# Grove_-_Directional_Light_Sensor_v1_0.net
KiCad netlist of a schematic drawn in EAGLE
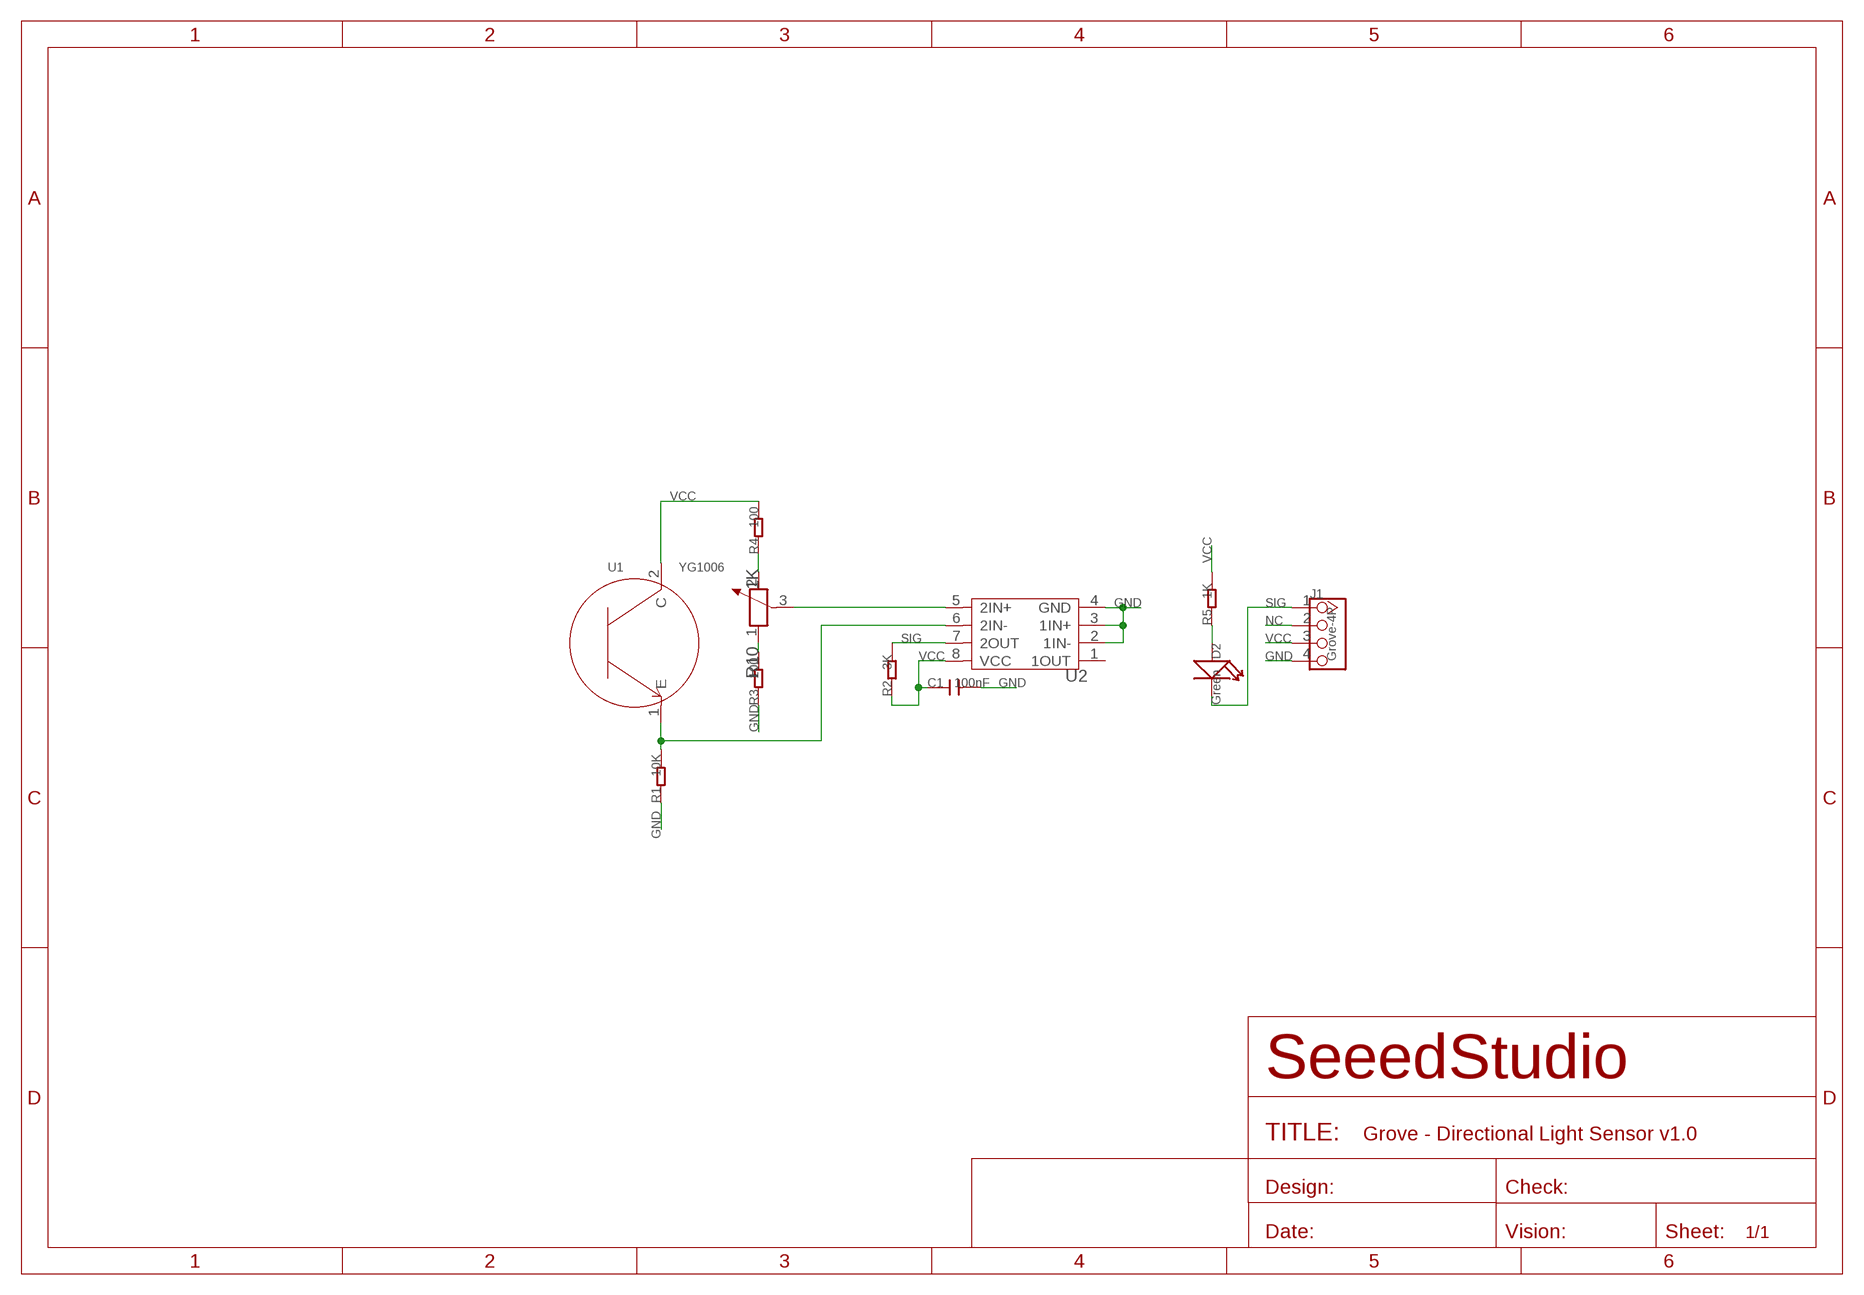
[diagram p0: schematic, sheet 1]

(export (version "E")
  (design (tool "Eeschema 10.0.6"))
  (components
    (comp (ref "C1")
      (value "100nF")
      (footprint "eagle-import:C0603")
      (libsource (lib "eagle-import") (part "C-0603"))
    )
    (comp (ref "D2")
      (value "Green")
      (footprint "eagle-import:LED-0603")
      (libsource (lib "eagle-import") (part "LED'0603'"))
    )
    (comp (ref "J1")
      (value "Grove-4P")
      (footprint "eagle-import:4P-2.0")
      (libsource (lib "eagle-import") (part "TWIG-4P-2.0-2.0"))
    )
    (comp (ref "R1")
      (value "10K")
      (footprint "eagle-import:R0603")
      (libsource (lib "eagle-import") (part "R-0603"))
    )
    (comp (ref "R2")
      (value "3K")
      (footprint "eagle-import:R0603")
      (libsource (lib "eagle-import") (part "R-0603"))
    )
    (comp (ref "R3")
      (value "100")
      (footprint "eagle-import:R0603")
      (libsource (lib "eagle-import") (part "R-0603"))
    )
    (comp (ref "R4")
      (value "100")
      (footprint "eagle-import:R0603")
      (libsource (lib "eagle-import") (part "R-0603"))
    )
    (comp (ref "R5")
      (value "1K")
      (footprint "eagle-import:R0603")
      (libsource (lib "eagle-import") (part "R-0603"))
    )
    (comp (ref "R10")
      (value "1K")
      (footprint "eagle-import:3P-SQUA-7X6.8")
      (libsource (lib "eagle-import") (part "R-POTENTIOMETER'3362'"))
    )
    (comp (ref "U1")
      (value "YG1006")
      (footprint "eagle-import:2P-2.54-5MM")
      (libsource (lib "eagle-import") (part "YG1006'YG1006'"))
    )
    (comp (ref "U2")
      (value "LM293D")
      (footprint "eagle-import:SOIC8-6.0")
      (libsource (lib "eagle-import") (part "LM293D"))
    )
  )
  (nets
    (net (code "1") (name "/GND") (class "Default")
      (node (ref "C1") (pin "2") (pinfunction "2_2") (pintype "passive"))
      (node (ref "J1") (pin "4") (pinfunction "4_4") (pintype "bidirectional"))
      (node (ref "R1") (pin "1") (pinfunction "1_1") (pintype "passive"))
      (node (ref "R3") (pin "1") (pinfunction "1_1") (pintype "passive"))
      (node (ref "U2") (pin "2") (pinfunction "1IN-_2") (pintype "input"))
      (node (ref "U2") (pin "3") (pinfunction "1IN+_3") (pintype "input"))
      (node (ref "U2") (pin "4") (pinfunction "GND_4") (pintype "power_in"))
    )
    (net (code "2") (name "/NC") (class "Default")
      (node (ref "J1") (pin "2") (pinfunction "2_2") (pintype "bidirectional"))
    )
    (net (code "3") (name "/SIG") (class "Default")
      (node (ref "D2") (pin "-") (pinfunction "-_-") (pintype "passive"))
      (node (ref "J1") (pin "1") (pinfunction "1_1") (pintype "bidirectional"))
      (node (ref "R2") (pin "2") (pinfunction "2_2") (pintype "passive"))
      (node (ref "U2") (pin "7") (pinfunction "2OUT_7") (pintype "output"))
    )
    (net (code "4") (name "/VCC") (class "Default")
      (node (ref "C1") (pin "1") (pinfunction "1_1") (pintype "passive"))
      (node (ref "J1") (pin "3") (pinfunction "3_3") (pintype "bidirectional"))
      (node (ref "R2") (pin "1") (pinfunction "1_1") (pintype "passive"))
      (node (ref "R4") (pin "2") (pinfunction "2_2") (pintype "passive"))
      (node (ref "R5") (pin "2") (pinfunction "2_2") (pintype "passive"))
      (node (ref "U1") (pin "2") (pinfunction "C_2") (pintype "bidirectional"))
      (node (ref "U2") (pin "8") (pinfunction "VCC_8") (pintype "power_in"))
    )
    (net (code "5") (name "Net-(D2-Pad+)") (class "Default")
      (node (ref "D2") (pin "+") (pinfunction "+_+") (pintype "passive"))
      (node (ref "R5") (pin "1") (pinfunction "1_1") (pintype "passive"))
    )
    (net (code "6") (name "Net-(R10-Pad1)") (class "Default")
      (node (ref "R10") (pin "1") (pinfunction "1_1") (pintype "passive"))
      (node (ref "R3") (pin "2") (pinfunction "2_2") (pintype "passive"))
    )
    (net (code "7") (name "Net-(R10-Pad2)") (class "Default")
      (node (ref "R10") (pin "2") (pinfunction "2_2") (pintype "passive"))
      (node (ref "R4") (pin "1") (pinfunction "1_1") (pintype "passive"))
    )
    (net (code "8") (name "Net-(U1-E)") (class "Default")
      (node (ref "R1") (pin "2") (pinfunction "2_2") (pintype "passive"))
      (node (ref "U1") (pin "1") (pinfunction "E_1") (pintype "bidirectional"))
      (node (ref "U2") (pin "6") (pinfunction "2IN-_6") (pintype "input"))
    )
    (net (code "9") (name "Net-(U2-2IN+)") (class "Default")
      (node (ref "R10") (pin "3") (pinfunction "3_3") (pintype "passive"))
      (node (ref "U2") (pin "5") (pinfunction "2IN+_5") (pintype "input"))
    )
    (net (code "10") (name "unconnected-(U2-1OUT-Pad1)") (class "Default")
      (node (ref "U2") (pin "1") (pinfunction "1OUT_1") (pintype "output"))
    )
  )
)
